# ir_dual.net
KiCad netlist of a schematic drawn in EAGLE
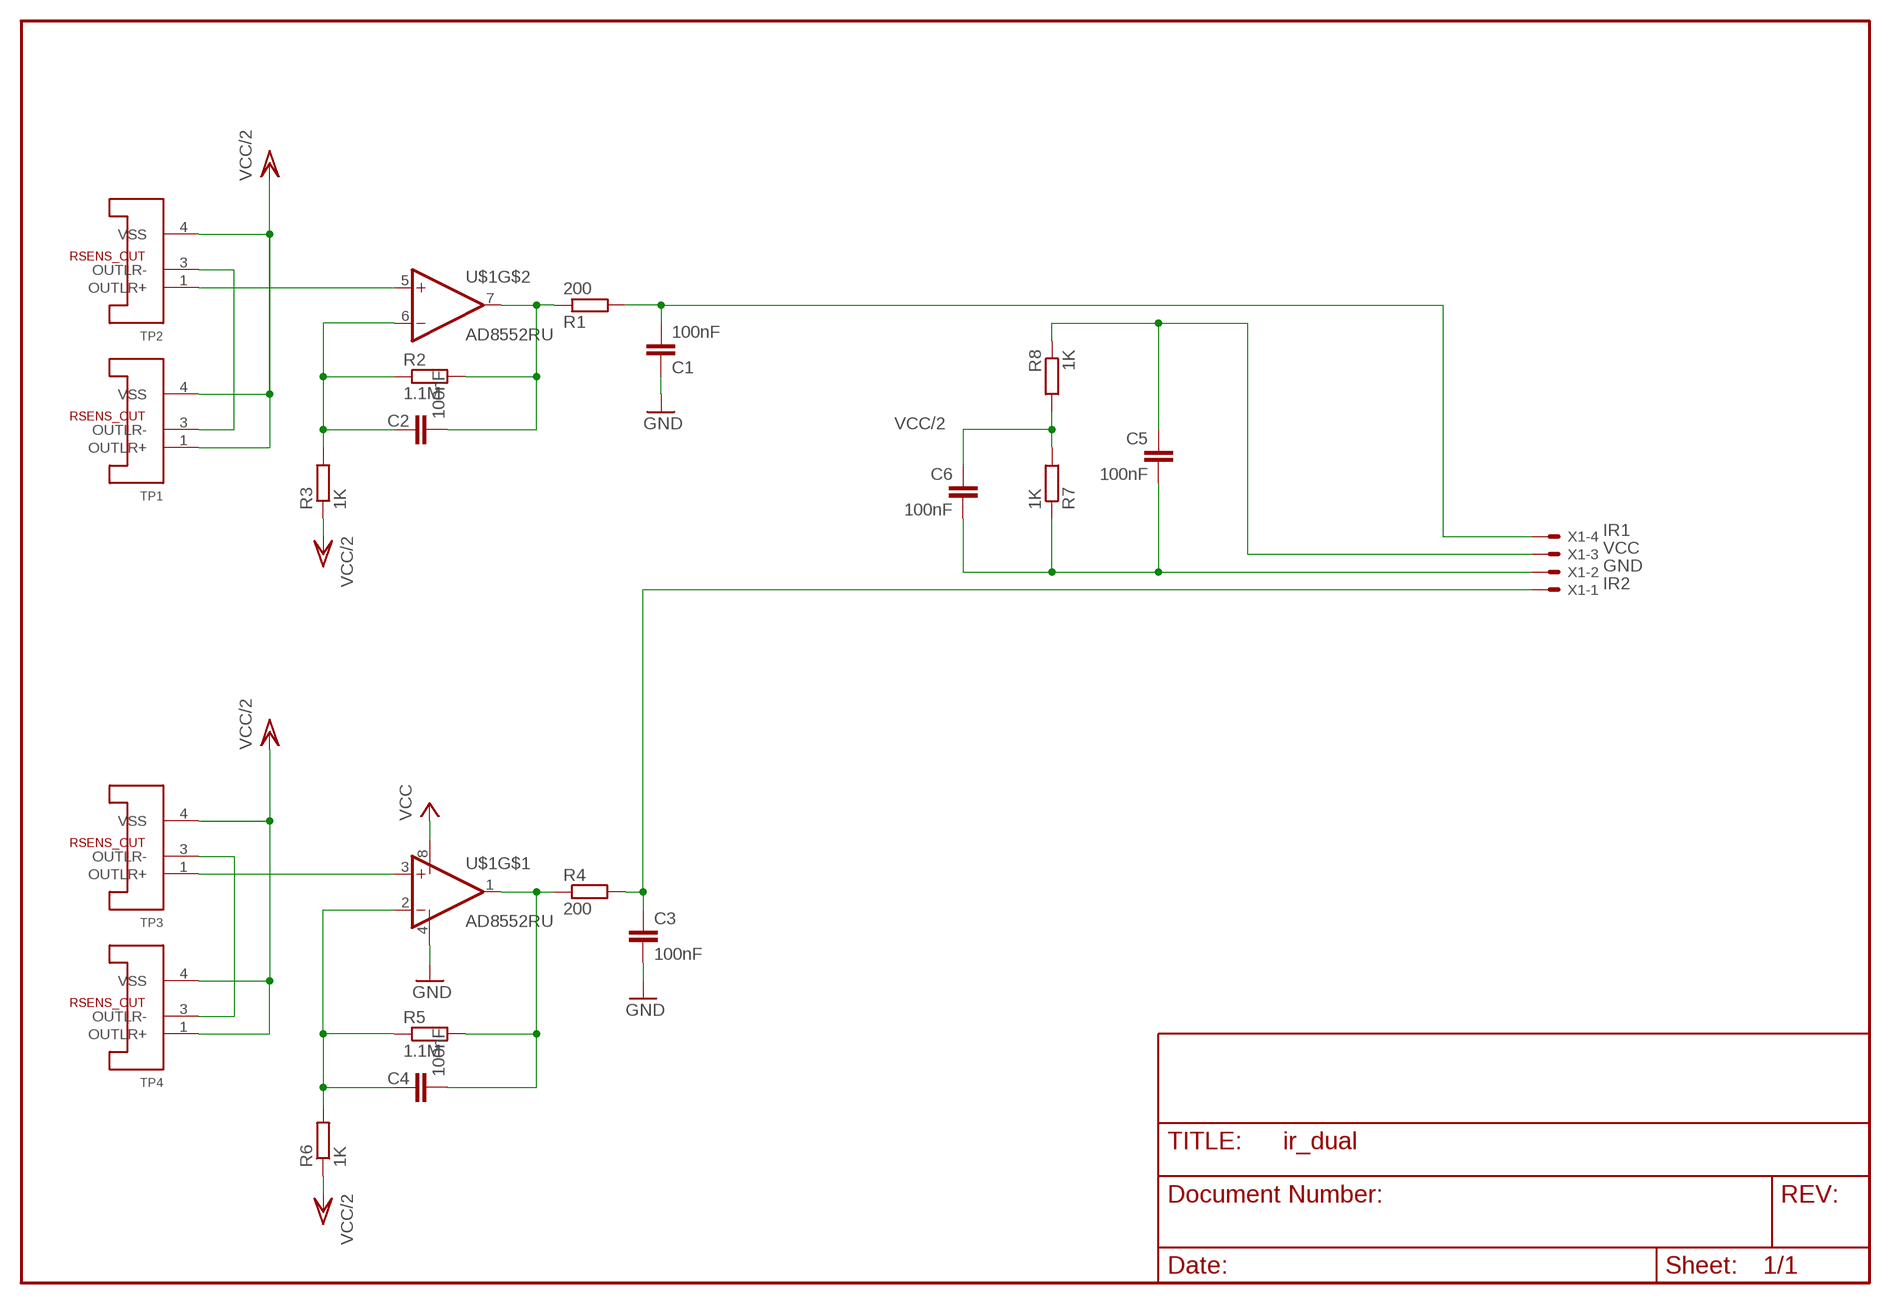
[diagram p0: schematic, sheet 1]

(export (version "E")
  (design (tool "Eeschema 10.0.6"))
  (components
    (comp (ref "C1")
      (value "100nF")
      (footprint "eagle-import:C0603")
      (libsource (lib "eagle-import") (part "C-EUC0603"))
    )
    (comp (ref "C2")
      (value "100nF")
      (footprint "eagle-import:C0603")
      (libsource (lib "eagle-import") (part "C-EUC0603"))
    )
    (comp (ref "C3")
      (value "100nF")
      (footprint "eagle-import:C0603")
      (libsource (lib "eagle-import") (part "C-EUC0603"))
    )
    (comp (ref "C4")
      (value "100nF")
      (footprint "eagle-import:C0603")
      (libsource (lib "eagle-import") (part "C-EUC0603"))
    )
    (comp (ref "C5")
      (value "100nF")
      (footprint "eagle-import:C0603")
      (libsource (lib "eagle-import") (part "C-EUC0603"))
    )
    (comp (ref "C6")
      (value "100nF")
      (footprint "eagle-import:C0603")
      (libsource (lib "eagle-import") (part "C-EUC0603"))
    )
    (comp (ref "R1")
      (value "200")
      (footprint "eagle-import:R0603")
      (libsource (lib "eagle-import") (part "R-EU_R0603"))
    )
    (comp (ref "R2")
      (value "1.1M")
      (footprint "eagle-import:R0603")
      (libsource (lib "eagle-import") (part "R-EU_R0603"))
    )
    (comp (ref "R3")
      (value "1K")
      (footprint "eagle-import:R0603")
      (libsource (lib "eagle-import") (part "R-EU_R0603"))
    )
    (comp (ref "R4")
      (value "200")
      (footprint "eagle-import:R0603")
      (libsource (lib "eagle-import") (part "R-EU_R0603"))
    )
    (comp (ref "R5")
      (value "1.1M")
      (footprint "eagle-import:R0603")
      (libsource (lib "eagle-import") (part "R-EU_R0603"))
    )
    (comp (ref "R6")
      (value "1K")
      (footprint "eagle-import:R0603")
      (libsource (lib "eagle-import") (part "R-EU_R0603"))
    )
    (comp (ref "R7")
      (value "1K")
      (footprint "eagle-import:R0603")
      (libsource (lib "eagle-import") (part "R-EU_R0603"))
    )
    (comp (ref "R8")
      (value "1K")
      (footprint "eagle-import:R0603")
      (libsource (lib "eagle-import") (part "R-EU_R0603"))
    )
    (comp (ref "TP1")
      (value "MLX90247")
      (footprint "eagle-import:TO39H")
      (libsource (lib "eagle-import") (part "MLX90247"))
    )
    (comp (ref "TP2")
      (value "MLX90247")
      (footprint "eagle-import:TO39H")
      (libsource (lib "eagle-import") (part "MLX90247"))
    )
    (comp (ref "TP3")
      (value "MLX90247")
      (footprint "eagle-import:TO39H")
      (libsource (lib "eagle-import") (part "MLX90247"))
    )
    (comp (ref "TP4")
      (value "MLX90247")
      (footprint "eagle-import:TO39H")
      (libsource (lib "eagle-import") (part "MLX90247"))
    )
    (comp (ref "U$1")
      (value "AD8552RU")
      (footprint "eagle-import:TSSOP8")
      (libsource (lib "eagle-import") (part "AD8552RU"))
    )
    (comp (ref "X1")
      (value "53048-04")
      (footprint "eagle-import:53048-04")
      (libsource (lib "eagle-import") (part "53?-04048"))
    )
  )
  (nets
    (net (code "1") (name "/IR1") (class "Default")
      (node (ref "C1") (pin "2") (pinfunction "2_2") (pintype "passive"))
      (node (ref "R1") (pin "2") (pinfunction "2_2") (pintype "passive"))
      (node (ref "X1") (pin "4") (pinfunction "S_4") (pintype "passive"))
    )
    (net (code "2") (name "/IR2") (class "Default")
      (node (ref "C3") (pin "1") (pinfunction "1_1") (pintype "passive"))
      (node (ref "R4") (pin "2") (pinfunction "2_2") (pintype "passive"))
      (node (ref "X1") (pin "1") (pinfunction "S_1") (pintype "passive"))
    )
    (net (code "3") (name "GND") (class "Default")
      (node (ref "C1") (pin "1") (pinfunction "1_1") (pintype "passive"))
      (node (ref "C3") (pin "2") (pinfunction "2_2") (pintype "passive"))
      (node (ref "C5") (pin "2") (pinfunction "2_2") (pintype "passive"))
      (node (ref "C6") (pin "2") (pinfunction "2_2") (pintype "passive"))
      (node (ref "R7") (pin "1") (pinfunction "1_1") (pintype "passive"))
      (node (ref "U$1") (pin "4") (pinfunction "V-_4") (pintype "power_in"))
      (node (ref "X1") (pin "2") (pinfunction "S_2") (pintype "passive"))
    )
    (net (code "4") (name "Net-(TP1-OUTLR-)") (class "Default")
      (node (ref "TP1") (pin "3") (pinfunction "OUTLR-_3") (pintype "bidirectional"))
      (node (ref "TP2") (pin "3") (pinfunction "OUTLR-_3") (pintype "bidirectional"))
    )
    (net (code "5") (name "Net-(TP2-OUTLR+)") (class "Default")
      (node (ref "TP2") (pin "1") (pinfunction "OUTLR+_1") (pintype "bidirectional"))
      (node (ref "U$1") (pin "5") (pinfunction "+IN_5") (pintype "input"))
    )
    (net (code "6") (name "Net-(TP3-OUTLR+)") (class "Default")
      (node (ref "TP3") (pin "1") (pinfunction "OUTLR+_1") (pintype "bidirectional"))
      (node (ref "U$1") (pin "3") (pinfunction "+IN_3") (pintype "input"))
    )
    (net (code "7") (name "Net-(TP3-OUTLR-)") (class "Default")
      (node (ref "TP3") (pin "3") (pinfunction "OUTLR-_3") (pintype "bidirectional"))
      (node (ref "TP4") (pin "3") (pinfunction "OUTLR-_3") (pintype "bidirectional"))
    )
    (net (code "8") (name "Net-(U$1A--IN)") (class "Default")
      (node (ref "C4") (pin "1") (pinfunction "1_1") (pintype "passive"))
      (node (ref "R5") (pin "1") (pinfunction "1_1") (pintype "passive"))
      (node (ref "R6") (pin "2") (pinfunction "2_2") (pintype "passive"))
      (node (ref "U$1") (pin "2") (pinfunction "-IN_2") (pintype "input"))
    )
    (net (code "9") (name "Net-(U$1A-OUT)") (class "Default")
      (node (ref "C4") (pin "2") (pinfunction "2_2") (pintype "passive"))
      (node (ref "R4") (pin "1") (pinfunction "1_1") (pintype "passive"))
      (node (ref "R5") (pin "2") (pinfunction "2_2") (pintype "passive"))
      (node (ref "U$1") (pin "1") (pinfunction "OUT_1") (pintype "output"))
    )
    (net (code "10") (name "Net-(U$1B--IN)") (class "Default")
      (node (ref "C2") (pin "1") (pinfunction "1_1") (pintype "passive"))
      (node (ref "R2") (pin "1") (pinfunction "1_1") (pintype "passive"))
      (node (ref "R3") (pin "2") (pinfunction "2_2") (pintype "passive"))
      (node (ref "U$1") (pin "6") (pinfunction "-IN_6") (pintype "input"))
    )
    (net (code "11") (name "Net-(U$1B-OUT)") (class "Default")
      (node (ref "C2") (pin "2") (pinfunction "2_2") (pintype "passive"))
      (node (ref "R1") (pin "1") (pinfunction "1_1") (pintype "passive"))
      (node (ref "R2") (pin "2") (pinfunction "2_2") (pintype "passive"))
      (node (ref "U$1") (pin "7") (pinfunction "OUT_7") (pintype "output"))
    )
    (net (code "12") (name "VCC") (class "Default")
      (node (ref "C5") (pin "1") (pinfunction "1_1") (pintype "passive"))
      (node (ref "R8") (pin "1") (pinfunction "1_1") (pintype "passive"))
      (node (ref "U$1") (pin "8") (pinfunction "V+_8") (pintype "power_in"))
      (node (ref "X1") (pin "3") (pinfunction "S_3") (pintype "passive"))
    )
    (net (code "13") (name "VCC{slash}2") (class "Default")
      (node (ref "C6") (pin "1") (pinfunction "1_1") (pintype "passive"))
      (node (ref "R3") (pin "1") (pinfunction "1_1") (pintype "passive"))
      (node (ref "R6") (pin "1") (pinfunction "1_1") (pintype "passive"))
      (node (ref "R7") (pin "2") (pinfunction "2_2") (pintype "passive"))
      (node (ref "R8") (pin "2") (pinfunction "2_2") (pintype "passive"))
      (node (ref "TP1") (pin "1") (pinfunction "OUTLR+_1") (pintype "bidirectional"))
      (node (ref "TP1") (pin "4") (pinfunction "VSS_4") (pintype "bidirectional"))
      (node (ref "TP2") (pin "4") (pinfunction "VSS_4") (pintype "bidirectional"))
      (node (ref "TP3") (pin "4") (pinfunction "VSS_4") (pintype "bidirectional"))
      (node (ref "TP4") (pin "1") (pinfunction "OUTLR+_1") (pintype "bidirectional"))
      (node (ref "TP4") (pin "4") (pinfunction "VSS_4") (pintype "bidirectional"))
    )
  )
)
